# isl3.net
KiCad netlist of a schematic drawn in EAGLE
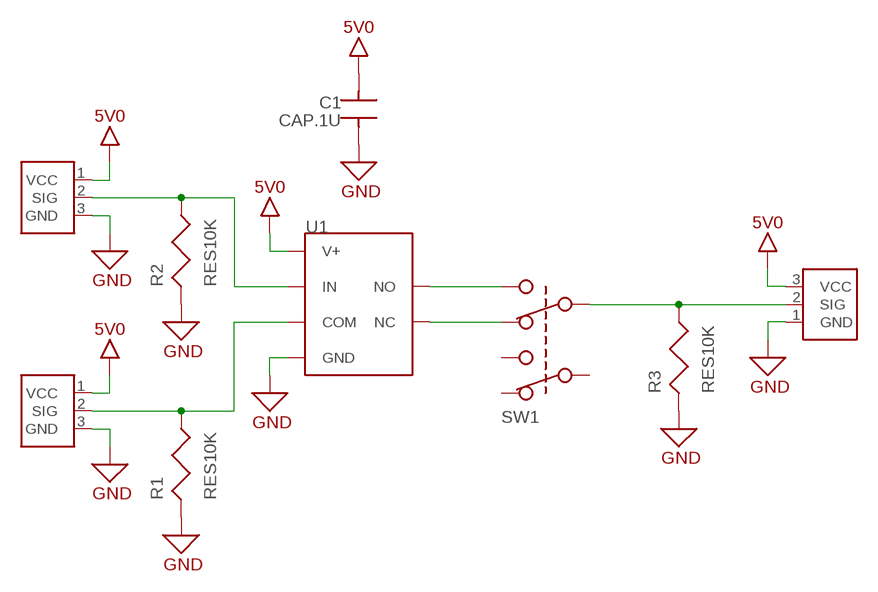
[diagram p0: schematic, sheet 1]

(export (version "E")
  (design (tool "Eeschema 10.0.6"))
  (components
    (comp (ref "C1")
      (value "CAP.1U")
      (footprint "eagle-import:SMT0603")
      (fields (field (name "MFR") "Murata") (field (name "MPN") "GRM188R71H104KA93D"))
      (libsource (lib "eagle-import") (part "CAP.1U"))
    )
    (comp (ref "J1")
      (value "BITSNAPINPUT")
      (footprint "eagle-import:BITSNAP_INPUT_MALE")
      (libsource (lib "eagle-import") (part "BITSNAPINPUT"))
    )
    (comp (ref "J2")
      (value "BITSNAPOUTPUT")
      (footprint "eagle-import:BITSNAP_OUTPUT_FEMALE")
      (libsource (lib "eagle-import") (part "BITSNAPOUTPUT"))
    )
    (comp (ref "J3")
      (value "BITSNAPINPUT")
      (footprint "eagle-import:BITSNAP_INPUT_MALE")
      (libsource (lib "eagle-import") (part "BITSNAPINPUT"))
    )
    (comp (ref "R1")
      (value "RES10K")
      (footprint "eagle-import:SMT0603")
      (fields (field (name "MFR") "Panasonic") (field (name "MPN") "ERJ-3EKF1002V "))
      (libsource (lib "eagle-import") (part "RES10K"))
    )
    (comp (ref "R2")
      (value "RES10K")
      (footprint "eagle-import:SMT0603")
      (fields (field (name "MFR") "Panasonic") (field (name "MPN") "ERJ-3EKF1002V "))
      (libsource (lib "eagle-import") (part "RES10K"))
    )
    (comp (ref "R3")
      (value "RES10K")
      (footprint "eagle-import:SMT0603")
      (fields (field (name "MFR") "Panasonic") (field (name "MPN") "ERJ-3EKF1002V "))
      (libsource (lib "eagle-import") (part "RES10K"))
    )
    (comp (ref "SW1")
      (value "AYZ0202AGRLC")
      (footprint "eagle-import:AYZ0202AGRLC")
      (libsource (lib "eagle-import") (part "AYZ0202AGRLC"))
    )
    (comp (ref "U1")
      (value "TS5A3160DBVR")
      (footprint "eagle-import:SOT23-6")
      (libsource (lib "eagle-import") (part "TS5A3160DBVR"))
    )
  )
  (nets
    (net (code "1") (name "5V0") (class "Default")
      (node (ref "C1") (pin "2") (pinfunction "2_2") (pintype "bidirectional"))
      (node (ref "J1") (pin "1") (pinfunction "VCC_1") (pintype "bidirectional"))
      (node (ref "J2") (pin "3") (pinfunction "VCC_3") (pintype "bidirectional"))
      (node (ref "J3") (pin "1") (pinfunction "VCC_1") (pintype "bidirectional"))
      (node (ref "U1") (pin "5") (pinfunction "V+_5") (pintype "bidirectional"))
    )
    (net (code "2") (name "GND") (class "Default")
      (node (ref "C1") (pin "1") (pinfunction "1_1") (pintype "bidirectional"))
      (node (ref "J1") (pin "3") (pinfunction "GND_3") (pintype "bidirectional"))
      (node (ref "J2") (pin "1") (pinfunction "GND_1") (pintype "bidirectional"))
      (node (ref "J3") (pin "3") (pinfunction "GND_3") (pintype "bidirectional"))
      (node (ref "R1") (pin "1") (pinfunction "1_1") (pintype "bidirectional"))
      (node (ref "R2") (pin "1") (pinfunction "1_1") (pintype "bidirectional"))
      (node (ref "R3") (pin "1") (pinfunction "1_1") (pintype "bidirectional"))
      (node (ref "U1") (pin "2") (pinfunction "GND_2") (pintype "bidirectional"))
    )
    (net (code "3") (name "Net-(J1-SIG)") (class "Default")
      (node (ref "J1") (pin "2") (pinfunction "SIG_2") (pintype "bidirectional"))
      (node (ref "R2") (pin "2") (pinfunction "2_2") (pintype "bidirectional"))
      (node (ref "U1") (pin "6") (pinfunction "IN_6") (pintype "bidirectional"))
    )
    (net (code "4") (name "Net-(J2-SIG)") (class "Default")
      (node (ref "J2") (pin "2") (pinfunction "SIG_2") (pintype "bidirectional"))
      (node (ref "R3") (pin "2") (pinfunction "2_2") (pintype "bidirectional"))
      (node (ref "SW1") (pin "5") (pinfunction "COM_B_5") (pintype "bidirectional"))
    )
    (net (code "5") (name "Net-(J3-SIG)") (class "Default")
      (node (ref "J3") (pin "2") (pinfunction "SIG_2") (pintype "bidirectional"))
      (node (ref "R1") (pin "2") (pinfunction "2_2") (pintype "bidirectional"))
      (node (ref "U1") (pin "4") (pinfunction "COM_4") (pintype "bidirectional"))
    )
    (net (code "6") (name "Net-(SW1-NC_B)") (class "Default")
      (node (ref "SW1") (pin "4") (pinfunction "NC_B_4") (pintype "bidirectional"))
      (node (ref "U1") (pin "3") (pinfunction "NC_3") (pintype "bidirectional"))
    )
    (net (code "7") (name "Net-(SW1-NO_B)") (class "Default")
      (node (ref "SW1") (pin "6") (pinfunction "NO_B_6") (pintype "bidirectional"))
      (node (ref "U1") (pin "1") (pinfunction "NO_1") (pintype "bidirectional"))
    )
    (net (code "8") (name "unconnected-(SW1-COM_A-Pad2)") (class "Default")
      (node (ref "SW1") (pin "2") (pinfunction "COM_A_2") (pintype "bidirectional"))
    )
    (net (code "9") (name "unconnected-(SW1-NC_A-Pad1)") (class "Default")
      (node (ref "SW1") (pin "1") (pinfunction "NC_A_1") (pintype "bidirectional"))
    )
    (net (code "10") (name "unconnected-(SW1-NO_A-Pad3)") (class "Default")
      (node (ref "SW1") (pin "3") (pinfunction "NO_A_3") (pintype "bidirectional"))
    )
  )
)
